# Eency_v01.net
KiCad netlist of a schematic drawn in EAGLE
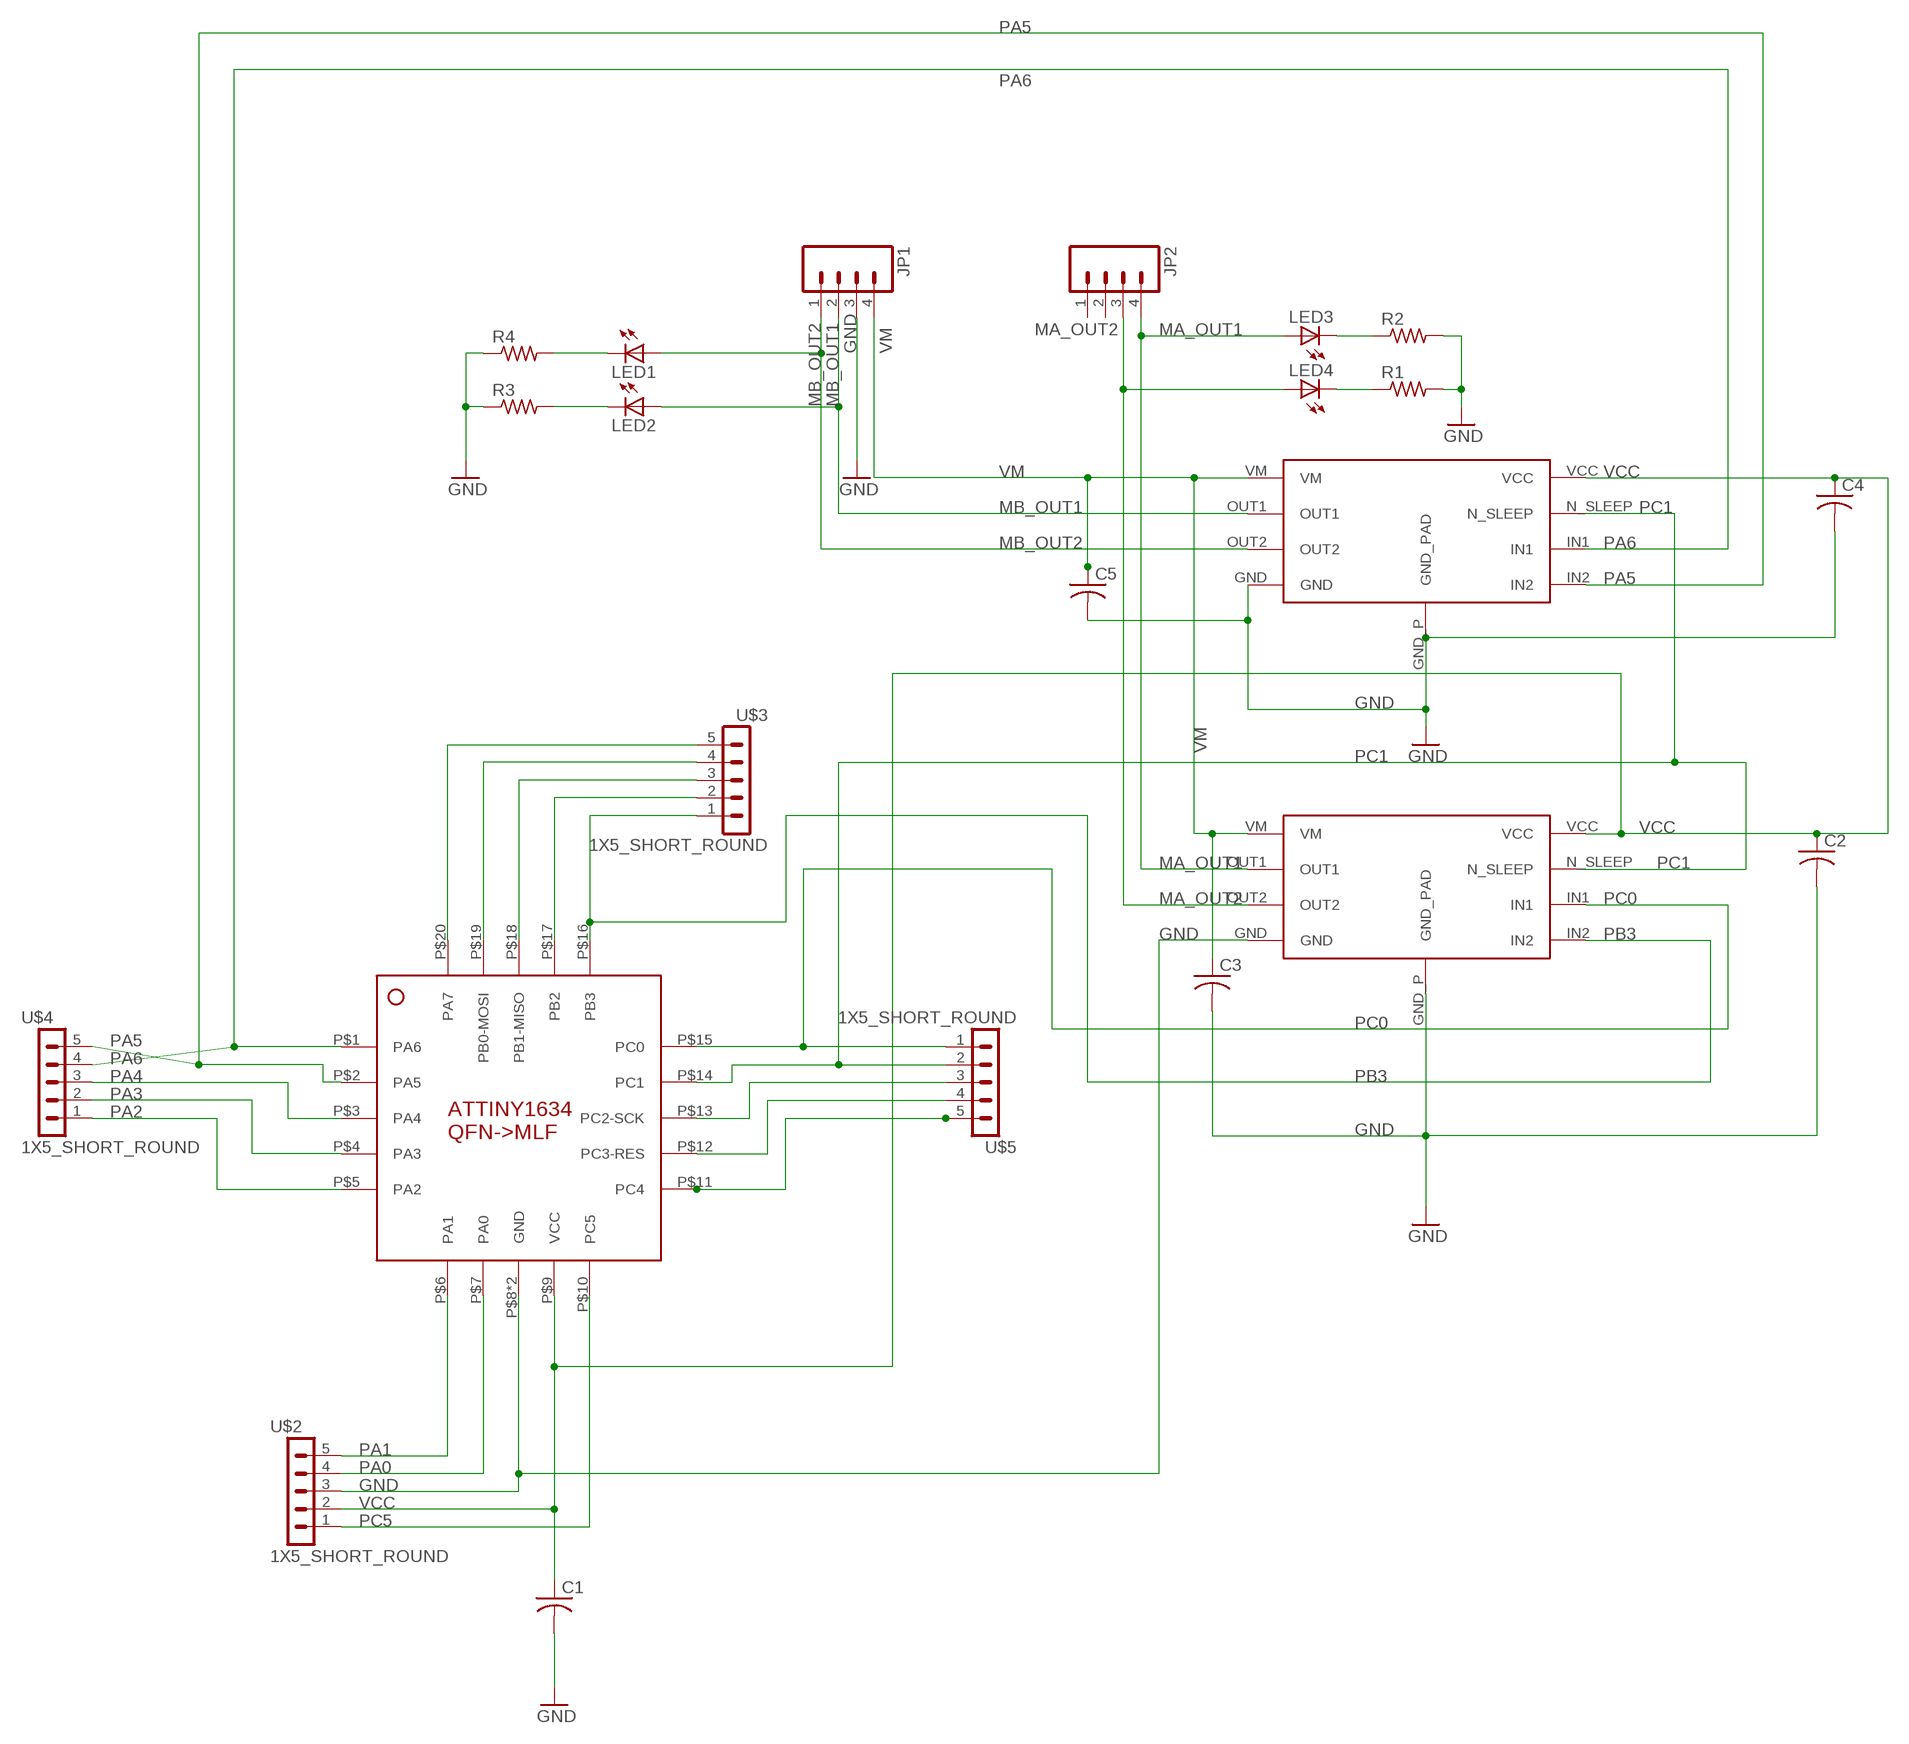
[diagram p0: schematic, sheet 1]

(export (version "E")
  (design (tool "Eeschema 10.0.6"))
  (components
    (comp (ref "C1")
      (value "C-USC0402K")
      (footprint "eagle-import:C0402K")
      (libsource (lib "eagle-import") (part "C-USC0402K"))
    )
    (comp (ref "C2")
      (value "C-USC0402K")
      (footprint "eagle-import:C0402K")
      (libsource (lib "eagle-import") (part "C-USC0402K"))
    )
    (comp (ref "C3")
      (value "C-USC0402K")
      (footprint "eagle-import:C0402K")
      (libsource (lib "eagle-import") (part "C-USC0402K"))
    )
    (comp (ref "C4")
      (value "C-USC0402K")
      (footprint "eagle-import:C0402K")
      (libsource (lib "eagle-import") (part "C-USC0402K"))
    )
    (comp (ref "C5")
      (value "C-USC0402K")
      (footprint "eagle-import:C0402K")
      (libsource (lib "eagle-import") (part "C-USC0402K"))
    )
    (comp (ref "JP1")
      (value "M04PTH")
      (footprint "eagle-import:1X04")
      (libsource (lib "eagle-import") (part "M04PTH"))
    )
    (comp (ref "JP2")
      (value "M04PTH")
      (footprint "eagle-import:1X04")
      (libsource (lib "eagle-import") (part "M04PTH"))
    )
    (comp (ref "LED1")
      (value "LEDSML0603")
      (footprint "eagle-import:SML0603")
      (libsource (lib "eagle-import") (part "LEDSML0603"))
    )
    (comp (ref "LED2")
      (value "LEDSML0603")
      (footprint "eagle-import:SML0603")
      (libsource (lib "eagle-import") (part "LEDSML0603"))
    )
    (comp (ref "LED3")
      (value "LEDSML0603")
      (footprint "eagle-import:SML0603")
      (libsource (lib "eagle-import") (part "LEDSML0603"))
    )
    (comp (ref "LED4")
      (value "LEDSML0603")
      (footprint "eagle-import:SML0603")
      (libsource (lib "eagle-import") (part "LEDSML0603"))
    )
    (comp (ref "R1")
      (value "R-US_R0402")
      (footprint "eagle-import:R0402")
      (libsource (lib "eagle-import") (part "R-US_R0402"))
    )
    (comp (ref "R2")
      (value "R-US_R0402")
      (footprint "eagle-import:R0402")
      (libsource (lib "eagle-import") (part "R-US_R0402"))
    )
    (comp (ref "R3")
      (value "R-US_R0402")
      (footprint "eagle-import:R0402")
      (libsource (lib "eagle-import") (part "R-US_R0402"))
    )
    (comp (ref "R4")
      (value "R-US_R0402")
      (footprint "eagle-import:R0402")
      (libsource (lib "eagle-import") (part "R-US_R0402"))
    )
    (comp (ref "U$1")
      (value "ATTINY1634")
      (footprint "eagle-import:MLF20_ATTINY13")
      (libsource (lib "eagle-import") (part "ATTINY1634"))
    )
    (comp (ref "U$2")
      (value "1X5_SHORT_ROUND")
      (footprint "eagle-import:1X5_SHORT_ROUND")
      (libsource (lib "eagle-import") (part "1X5_SHORT_ROUND"))
    )
    (comp (ref "U$3")
      (value "1X5_SHORT_ROUND")
      (footprint "eagle-import:1X5_SHORT_ROUND")
      (libsource (lib "eagle-import") (part "1X5_SHORT_ROUND"))
    )
    (comp (ref "U$4")
      (value "1X5_SHORT_ROUND")
      (footprint "eagle-import:1X5_SHORT_ROUND")
      (libsource (lib "eagle-import") (part "1X5_SHORT_ROUND"))
    )
    (comp (ref "U$5")
      (value "1X5_SHORT_ROUND")
      (footprint "eagle-import:1X5_SHORT_ROUND")
      (libsource (lib "eagle-import") (part "1X5_SHORT_ROUND"))
    )
    (comp (ref "U$8")
      (value "DRV8837")
      (footprint "eagle-import:WSON-8")
      (libsource (lib "eagle-import") (part "DRV8837"))
    )
    (comp (ref "U$9")
      (value "DRV8837")
      (footprint "eagle-import:WSON-8")
      (libsource (lib "eagle-import") (part "DRV8837"))
    )
  )
  (nets
    (net (code "1") (name "/MA_OUT1") (class "Default")
      (node (ref "JP2") (pin "4") (pinfunction "4_4") (pintype "passive"))
      (node (ref "LED3") (pin "A") (pinfunction "A_A") (pintype "passive"))
      (node (ref "U$8") (pin "OUT1") (pinfunction "OUT1_OUT1") (pintype "bidirectional"))
    )
    (net (code "2") (name "/MA_OUT2") (class "Default")
      (node (ref "JP2") (pin "3") (pinfunction "3_3") (pintype "passive"))
      (node (ref "LED4") (pin "A") (pinfunction "A_A") (pintype "passive"))
      (node (ref "U$8") (pin "OUT2") (pinfunction "OUT2_OUT2") (pintype "bidirectional"))
    )
    (net (code "3") (name "/MB_OUT1") (class "Default")
      (node (ref "JP1") (pin "2") (pinfunction "2_2") (pintype "passive"))
      (node (ref "LED2") (pin "A") (pinfunction "A_A") (pintype "passive"))
      (node (ref "U$9") (pin "OUT1") (pinfunction "OUT1_OUT1") (pintype "bidirectional"))
    )
    (net (code "4") (name "/MB_OUT2") (class "Default")
      (node (ref "JP1") (pin "1") (pinfunction "1_1") (pintype "passive"))
      (node (ref "LED1") (pin "A") (pinfunction "A_A") (pintype "passive"))
      (node (ref "U$9") (pin "OUT2") (pinfunction "OUT2_OUT2") (pintype "bidirectional"))
    )
    (net (code "5") (name "/PA0") (class "Default")
      (node (ref "U$1") (pin "P$7") (pinfunction "PA0_P$7") (pintype "bidirectional"))
      (node (ref "U$2") (pin "4") (pinfunction "5_4") (pintype "passive"))
    )
    (net (code "6") (name "/PA1") (class "Default")
      (node (ref "U$1") (pin "P$6") (pinfunction "PA1_P$6") (pintype "bidirectional"))
      (node (ref "U$2") (pin "5") (pinfunction "6_5") (pintype "passive"))
    )
    (net (code "7") (name "/PA2") (class "Default")
      (node (ref "U$1") (pin "P$5") (pinfunction "PA2_P$5") (pintype "bidirectional"))
      (node (ref "U$4") (pin "1") (pinfunction "2_1") (pintype "passive"))
    )
    (net (code "8") (name "/PA3") (class "Default")
      (node (ref "U$1") (pin "P$4") (pinfunction "PA3_P$4") (pintype "bidirectional"))
      (node (ref "U$4") (pin "2") (pinfunction "3_2") (pintype "passive"))
    )
    (net (code "9") (name "/PA4") (class "Default")
      (node (ref "U$1") (pin "P$3") (pinfunction "PA4_P$3") (pintype "bidirectional"))
      (node (ref "U$4") (pin "3") (pinfunction "4_3") (pintype "passive"))
    )
    (net (code "10") (name "/PA5") (class "Default")
      (node (ref "U$1") (pin "P$2") (pinfunction "PA5_P$2") (pintype "bidirectional"))
      (node (ref "U$4") (pin "5") (pinfunction "6_5") (pintype "passive"))
      (node (ref "U$9") (pin "IN2") (pinfunction "IN2_IN2") (pintype "bidirectional"))
    )
    (net (code "11") (name "/PA6") (class "Default")
      (node (ref "U$1") (pin "P$1") (pinfunction "PA6_P$1") (pintype "bidirectional"))
      (node (ref "U$4") (pin "4") (pinfunction "5_4") (pintype "passive"))
      (node (ref "U$9") (pin "IN1") (pinfunction "IN1_IN1") (pintype "bidirectional"))
    )
    (net (code "12") (name "/PB3") (class "Default")
      (node (ref "U$1") (pin "P$16") (pinfunction "PB3_P$16") (pintype "bidirectional"))
      (node (ref "U$3") (pin "1") (pinfunction "2_1") (pintype "passive"))
      (node (ref "U$8") (pin "IN2") (pinfunction "IN2_IN2") (pintype "bidirectional"))
    )
    (net (code "13") (name "/PC0") (class "Default")
      (node (ref "U$1") (pin "P$15") (pinfunction "PC0_P$15") (pintype "bidirectional"))
      (node (ref "U$5") (pin "1") (pinfunction "2_1") (pintype "passive"))
      (node (ref "U$8") (pin "IN1") (pinfunction "IN1_IN1") (pintype "bidirectional"))
    )
    (net (code "14") (name "/PC1") (class "Default")
      (node (ref "U$1") (pin "P$14") (pinfunction "PC1_P$14") (pintype "bidirectional"))
      (node (ref "U$5") (pin "2") (pinfunction "3_2") (pintype "passive"))
      (node (ref "U$8") (pin "N_SLEEP") (pinfunction "N_SLEEP_N_SLEEP") (pintype "bidirectional"))
      (node (ref "U$9") (pin "N_SLEEP") (pinfunction "N_SLEEP_N_SLEEP") (pintype "bidirectional"))
    )
    (net (code "15") (name "/PC5") (class "Default")
      (node (ref "U$1") (pin "P$10") (pinfunction "PC5_P$10") (pintype "bidirectional"))
      (node (ref "U$2") (pin "1") (pinfunction "2_1") (pintype "passive"))
    )
    (net (code "16") (name "/VCC") (class "Default")
      (node (ref "C1") (pin "1") (pinfunction "1_1") (pintype "passive"))
      (node (ref "C2") (pin "1") (pinfunction "1_1") (pintype "passive"))
      (node (ref "C4") (pin "1") (pinfunction "1_1") (pintype "passive"))
      (node (ref "U$1") (pin "P$9") (pinfunction "VCC_P$9") (pintype "bidirectional"))
      (node (ref "U$2") (pin "2") (pinfunction "3_2") (pintype "passive"))
      (node (ref "U$8") (pin "VCC") (pinfunction "VCC_VCC") (pintype "bidirectional"))
      (node (ref "U$9") (pin "VCC") (pinfunction "VCC_VCC") (pintype "bidirectional"))
    )
    (net (code "17") (name "/VM") (class "Default")
      (node (ref "C3") (pin "1") (pinfunction "1_1") (pintype "passive"))
      (node (ref "C5") (pin "1") (pinfunction "1_1") (pintype "passive"))
      (node (ref "JP1") (pin "4") (pinfunction "4_4") (pintype "passive"))
      (node (ref "U$8") (pin "VM") (pinfunction "VM_VM") (pintype "bidirectional"))
      (node (ref "U$9") (pin "VM") (pinfunction "VM_VM") (pintype "bidirectional"))
    )
    (net (code "18") (name "GND") (class "Default")
      (node (ref "C1") (pin "2") (pinfunction "2_2") (pintype "passive"))
      (node (ref "C2") (pin "2") (pinfunction "2_2") (pintype "passive"))
      (node (ref "C3") (pin "2") (pinfunction "2_2") (pintype "passive"))
      (node (ref "C4") (pin "2") (pinfunction "2_2") (pintype "passive"))
      (node (ref "C5") (pin "2") (pinfunction "2_2") (pintype "passive"))
      (node (ref "JP1") (pin "3") (pinfunction "3_3") (pintype "passive"))
      (node (ref "R1") (pin "2") (pinfunction "2_2") (pintype "passive"))
      (node (ref "R2") (pin "2") (pinfunction "2_2") (pintype "passive"))
      (node (ref "R3") (pin "1") (pinfunction "1_1") (pintype "passive"))
      (node (ref "R4") (pin "1") (pinfunction "1_1") (pintype "passive"))
      (node (ref "U$1") (pin "P$21") (pinfunction "GND_P$21") (pintype "bidirectional"))
      (node (ref "U$1") (pin "P$8") (pinfunction "GND_P$8") (pintype "bidirectional"))
      (node (ref "U$2") (pin "3") (pinfunction "4_3") (pintype "passive"))
      (node (ref "U$8") (pin "GND") (pinfunction "GND_GND") (pintype "bidirectional"))
      (node (ref "U$8") (pin "GND_P") (pinfunction "GND_PAD_GND_P") (pintype "bidirectional"))
      (node (ref "U$9") (pin "GND") (pinfunction "GND_GND") (pintype "bidirectional"))
      (node (ref "U$9") (pin "GND_P") (pinfunction "GND_PAD_GND_P") (pintype "bidirectional"))
    )
    (net (code "19") (name "Net-(LED1-PadC)") (class "Default")
      (node (ref "LED1") (pin "C") (pinfunction "C_C") (pintype "passive"))
      (node (ref "R4") (pin "2") (pinfunction "2_2") (pintype "passive"))
    )
    (net (code "20") (name "Net-(LED2-PadC)") (class "Default")
      (node (ref "LED2") (pin "C") (pinfunction "C_C") (pintype "passive"))
      (node (ref "R3") (pin "2") (pinfunction "2_2") (pintype "passive"))
    )
    (net (code "21") (name "Net-(LED3-PadC)") (class "Default")
      (node (ref "LED3") (pin "C") (pinfunction "C_C") (pintype "passive"))
      (node (ref "R2") (pin "1") (pinfunction "1_1") (pintype "passive"))
    )
    (net (code "22") (name "Net-(LED4-PadC)") (class "Default")
      (node (ref "LED4") (pin "C") (pinfunction "C_C") (pintype "passive"))
      (node (ref "R1") (pin "1") (pinfunction "1_1") (pintype "passive"))
    )
    (net (code "23") (name "Net-(U$1-PA7)") (class "Default")
      (node (ref "U$1") (pin "P$20") (pinfunction "PA7_P$20") (pintype "bidirectional"))
      (node (ref "U$3") (pin "5") (pinfunction "6_5") (pintype "passive"))
    )
    (net (code "24") (name "Net-(U$1-PB0-MOSI)") (class "Default")
      (node (ref "U$1") (pin "P$19") (pinfunction "PB0-MOSI_P$19") (pintype "bidirectional"))
      (node (ref "U$3") (pin "4") (pinfunction "5_4") (pintype "passive"))
    )
    (net (code "25") (name "Net-(U$1-PB1-MISO)") (class "Default")
      (node (ref "U$1") (pin "P$18") (pinfunction "PB1-MISO_P$18") (pintype "bidirectional"))
      (node (ref "U$3") (pin "3") (pinfunction "4_3") (pintype "passive"))
    )
    (net (code "26") (name "Net-(U$1-PB2)") (class "Default")
      (node (ref "U$1") (pin "P$17") (pinfunction "PB2_P$17") (pintype "bidirectional"))
      (node (ref "U$3") (pin "2") (pinfunction "3_2") (pintype "passive"))
    )
    (net (code "27") (name "Net-(U$1-PC2-SCK)") (class "Default")
      (node (ref "U$1") (pin "P$13") (pinfunction "PC2-SCK_P$13") (pintype "bidirectional"))
      (node (ref "U$5") (pin "3") (pinfunction "4_3") (pintype "passive"))
    )
    (net (code "28") (name "Net-(U$1-PC3-RES)") (class "Default")
      (node (ref "U$1") (pin "P$12") (pinfunction "PC3-RES_P$12") (pintype "bidirectional"))
      (node (ref "U$5") (pin "4") (pinfunction "5_4") (pintype "passive"))
    )
    (net (code "29") (name "Net-(U$1-PC4)") (class "Default")
      (node (ref "U$1") (pin "P$11") (pinfunction "PC4_P$11") (pintype "bidirectional"))
      (node (ref "U$5") (pin "5") (pinfunction "6_5") (pintype "passive"))
    )
    (net (code "30") (name "unconnected-(JP2-Pad1)") (class "Default")
      (node (ref "JP2") (pin "1") (pinfunction "1_1") (pintype "passive"))
    )
    (net (code "31") (name "unconnected-(JP2-Pad2)") (class "Default")
      (node (ref "JP2") (pin "2") (pinfunction "2_2") (pintype "passive"))
    )
  )
)
